# Sheet1.net
KiCad netlist of a schematic drawn in Altium Designer
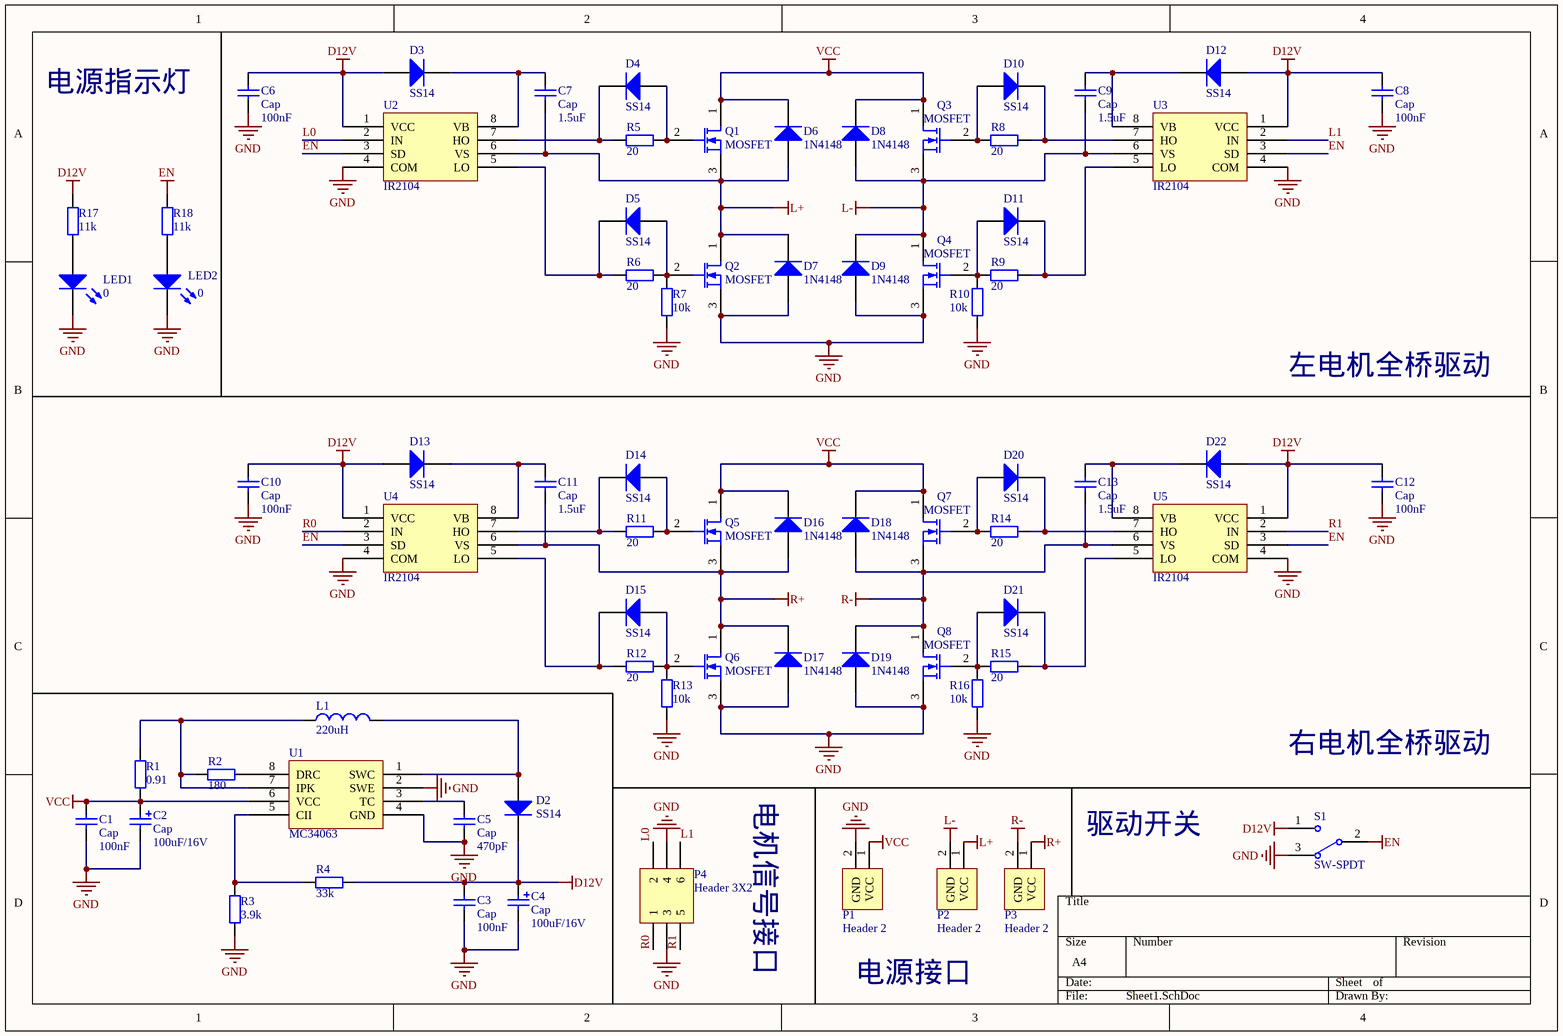
[diagram p0: Sheet1.SchDoc]

(export (version "E")
  (design (tool "Eeschema 10.0.6"))
  (components
    (comp (ref "C1")
      (value "Cap")
      (footprint "0603C")
      (description "Capacitor")
      (fields (field (name "ALTIUM_VALUE") "100nF") (field (name "PUBLISHER") "Altium Limited"))
      (libsource (lib "Schlib1") (part "Cap"))
    )
    (comp (ref "C2")
      (value "Cap")
      (footprint "电解电容")
      (description "Capacitor")
      (fields (field (name "ALTIUM_VALUE") "100uF/16V") (field (name "PUBLISHER") "Altium Limited"))
      (libsource (lib "Schlib1") (part "Cap2"))
    )
    (comp (ref "C3")
      (value "Cap")
      (footprint "0603C")
      (description "Capacitor")
      (fields (field (name "ALTIUM_VALUE") "100nF") (field (name "PUBLISHER") "Altium Limited"))
      (libsource (lib "Schlib1") (part "Cap"))
    )
    (comp (ref "C4")
      (value "Cap")
      (footprint "电解电容")
      (description "Capacitor")
      (fields (field (name "ALTIUM_VALUE") "100uF/16V") (field (name "PUBLISHER") "Altium Limited"))
      (libsource (lib "Schlib1") (part "Cap2"))
    )
    (comp (ref "C5")
      (value "Cap")
      (footprint "0603C")
      (description "Capacitor")
      (fields (field (name "ALTIUM_VALUE") "470pF") (field (name "PUBLISHER") "Altium Limited"))
      (libsource (lib "Schlib1") (part "Cap"))
    )
    (comp (ref "C6")
      (value "Cap")
      (footprint "0603C")
      (description "Capacitor")
      (fields (field (name "ALTIUM_VALUE") "100nF") (field (name "PUBLISHER") "Altium Limited"))
      (libsource (lib "Schlib1") (part "Cap"))
    )
    (comp (ref "C7")
      (value "Cap")
      (footprint "0603C")
      (description "Capacitor")
      (fields (field (name "ALTIUM_VALUE") "1.5uF") (field (name "PUBLISHER") "Altium Limited"))
      (libsource (lib "Schlib1") (part "Cap"))
    )
    (comp (ref "C8")
      (value "Cap")
      (footprint "0603C")
      (description "Capacitor")
      (fields (field (name "ALTIUM_VALUE") "100nF") (field (name "PUBLISHER") "Altium Limited"))
      (libsource (lib "Schlib1") (part "Cap"))
    )
    (comp (ref "C9")
      (value "Cap")
      (footprint "0603C")
      (description "Capacitor")
      (fields (field (name "ALTIUM_VALUE") "1.5uF") (field (name "PUBLISHER") "Altium Limited"))
      (libsource (lib "Schlib1") (part "Cap"))
    )
    (comp (ref "C10")
      (value "Cap")
      (footprint "0603C")
      (description "Capacitor")
      (fields (field (name "ALTIUM_VALUE") "100nF") (field (name "PUBLISHER") "Altium Limited"))
      (libsource (lib "Schlib1") (part "Cap"))
    )
    (comp (ref "C11")
      (value "Cap")
      (footprint "0603C")
      (description "Capacitor")
      (fields (field (name "ALTIUM_VALUE") "1.5uF") (field (name "PUBLISHER") "Altium Limited"))
      (libsource (lib "Schlib1") (part "Cap"))
    )
    (comp (ref "C12")
      (value "Cap")
      (footprint "0603C")
      (description "Capacitor")
      (fields (field (name "ALTIUM_VALUE") "100nF") (field (name "PUBLISHER") "Altium Limited"))
      (libsource (lib "Schlib1") (part "Cap"))
    )
    (comp (ref "C13")
      (value "Cap")
      (footprint "0603C")
      (description "Capacitor")
      (fields (field (name "ALTIUM_VALUE") "1.5uF") (field (name "PUBLISHER") "Altium Limited"))
      (libsource (lib "Schlib1") (part "Cap"))
    )
    (comp (ref "D2")
      (value "SS14")
      (footprint "ss54")
      (description "Default Diode")
      (fields (field (name "PUBLISHER") "Altium Limited"))
      (libsource (lib "Schlib1") (part "Diode_1"))
    )
    (comp (ref "D3")
      (value "SS14")
      (footprint "ss54")
      (description "Default Diode")
      (fields (field (name "PUBLISHER") "Altium Limited"))
      (libsource (lib "Schlib1") (part "Diode_1"))
    )
    (comp (ref "D4")
      (value "SS14")
      (footprint "ss54")
      (description "Default Diode")
      (fields (field (name "PUBLISHER") "Altium Limited"))
      (libsource (lib "Schlib1") (part "Diode_1"))
    )
    (comp (ref "D5")
      (value "SS14")
      (footprint "ss54")
      (description "Default Diode")
      (fields (field (name "PUBLISHER") "Altium Limited"))
      (libsource (lib "Schlib1") (part "Diode_1"))
    )
    (comp (ref "D6")
      (value "1N4148")
      (footprint "SOD123")
      (description "Default Diode")
      (fields (field (name "PUBLISHER") "Altium Limited"))
      (libsource (lib "Schlib1") (part "Diode_2"))
    )
    (comp (ref "D7")
      (value "1N4148")
      (footprint "SOD123")
      (description "Default Diode")
      (fields (field (name "PUBLISHER") "Altium Limited"))
      (libsource (lib "Schlib1") (part "Diode_2"))
    )
    (comp (ref "D8")
      (value "1N4148")
      (footprint "SOD123")
      (description "Default Diode")
      (fields (field (name "PUBLISHER") "Altium Limited"))
      (libsource (lib "Schlib1") (part "Diode_2"))
    )
    (comp (ref "D9")
      (value "1N4148")
      (footprint "SOD123")
      (description "Default Diode")
      (fields (field (name "PUBLISHER") "Altium Limited"))
      (libsource (lib "Schlib1") (part "Diode_2"))
    )
    (comp (ref "D10")
      (value "SS14")
      (footprint "ss54")
      (description "Default Diode")
      (fields (field (name "PUBLISHER") "Altium Limited"))
      (libsource (lib "Schlib1") (part "Diode_1"))
    )
    (comp (ref "D11")
      (value "SS14")
      (footprint "ss54")
      (description "Default Diode")
      (fields (field (name "PUBLISHER") "Altium Limited"))
      (libsource (lib "Schlib1") (part "Diode_1"))
    )
    (comp (ref "D12")
      (value "SS14")
      (footprint "ss54")
      (description "Default Diode")
      (fields (field (name "PUBLISHER") "Altium Limited"))
      (libsource (lib "Schlib1") (part "Diode_1"))
    )
    (comp (ref "D13")
      (value "SS14")
      (footprint "ss54")
      (description "Default Diode")
      (fields (field (name "PUBLISHER") "Altium Limited"))
      (libsource (lib "Schlib1") (part "Diode_1"))
    )
    (comp (ref "D14")
      (value "SS14")
      (footprint "ss54")
      (description "Default Diode")
      (fields (field (name "PUBLISHER") "Altium Limited"))
      (libsource (lib "Schlib1") (part "Diode_1"))
    )
    (comp (ref "D15")
      (value "SS14")
      (footprint "ss54")
      (description "Default Diode")
      (fields (field (name "PUBLISHER") "Altium Limited"))
      (libsource (lib "Schlib1") (part "Diode_1"))
    )
    (comp (ref "D16")
      (value "1N4148")
      (footprint "SOD123")
      (description "Default Diode")
      (fields (field (name "PUBLISHER") "Altium Limited"))
      (libsource (lib "Schlib1") (part "Diode_2"))
    )
    (comp (ref "D17")
      (value "1N4148")
      (footprint "SOD123")
      (description "Default Diode")
      (fields (field (name "PUBLISHER") "Altium Limited"))
      (libsource (lib "Schlib1") (part "Diode_2"))
    )
    (comp (ref "D18")
      (value "1N4148")
      (footprint "SOD123")
      (description "Default Diode")
      (fields (field (name "PUBLISHER") "Altium Limited"))
      (libsource (lib "Schlib1") (part "Diode_2"))
    )
    (comp (ref "D19")
      (value "1N4148")
      (footprint "SOD123")
      (description "Default Diode")
      (fields (field (name "PUBLISHER") "Altium Limited"))
      (libsource (lib "Schlib1") (part "Diode_2"))
    )
    (comp (ref "D20")
      (value "SS14")
      (footprint "ss54")
      (description "Default Diode")
      (fields (field (name "PUBLISHER") "Altium Limited"))
      (libsource (lib "Schlib1") (part "Diode_1"))
    )
    (comp (ref "D21")
      (value "SS14")
      (footprint "ss54")
      (description "Default Diode")
      (fields (field (name "PUBLISHER") "Altium Limited"))
      (libsource (lib "Schlib1") (part "Diode_1"))
    )
    (comp (ref "D22")
      (value "SS14")
      (footprint "ss54")
      (description "Default Diode")
      (fields (field (name "PUBLISHER") "Altium Limited"))
      (libsource (lib "Schlib1") (part "Diode_1"))
    )
    (comp (ref "L1")
      (value "220uH")
      (footprint "cd54")
      (description "Inductor")
      (fields (field (name "PUBLISHER") "Altium Limited"))
      (libsource (lib "Schlib1") (part "Inductor_2"))
    )
    (comp (ref "LED1")
      (value "0")
      (footprint "0603C")
      (description "Typical RED, GREEN, YELLOW, AMBER GaAs LED")
      (fields (field (name "PUBLISHER") "Altium Limited"))
      (libsource (lib "Schlib1") (part "LED2"))
    )
    (comp (ref "LED2")
      (value "0")
      (footprint "0603C")
      (description "Typical RED, GREEN, YELLOW, AMBER GaAs LED")
      (fields (field (name "PUBLISHER") "Altium Limited"))
      (libsource (lib "Schlib1") (part "LED2"))
    )
    (comp (ref "P1")
      (value "Header 2")
      (footprint "VCCBAT")
      (description "Header, 2-Pin")
      (fields (field (name "PUBLISHER") "Altium Limited"))
      (libsource (lib "Schlib1") (part "Header 2_2"))
    )
    (comp (ref "P2")
      (value "Header 2")
      (footprint "VCCBAT")
      (description "Header, 2-Pin")
      (fields (field (name "PUBLISHER") "Altium Limited"))
      (libsource (lib "Schlib1") (part "Header 2_2"))
    )
    (comp (ref "P3")
      (value "Header 2")
      (footprint "VCCBAT")
      (description "Header, 2-Pin")
      (fields (field (name "PUBLISHER") "Altium Limited"))
      (libsource (lib "Schlib1") (part "Header 2_2"))
    )
    (comp (ref "P4")
      (value "Header 3X2")
      (footprint "HDR2X3")
      (description "Header, 3-Pin, Dual row")
      (fields (field (name "PUBLISHER") "Altium Limited"))
      (libsource (lib "Miscellaneous Connectors") (part "Header 3X2"))
    )
    (comp (ref "Q1") (value "MOSFET") (footprint "DPAK-1") (libsource (lib "Schlib1") (part "MOSFET-N")))
    (comp (ref "Q2") (value "MOSFET") (footprint "DPAK-1") (libsource (lib "Schlib1") (part "MOSFET-N")))
    (comp (ref "Q3") (value "MOSFET") (footprint "DPAK-1") (libsource (lib "Schlib1") (part "MOSFET-N")))
    (comp (ref "Q4") (value "MOSFET") (footprint "DPAK-1") (libsource (lib "Schlib1") (part "MOSFET-N")))
    (comp (ref "Q5") (value "MOSFET") (footprint "DPAK-1") (libsource (lib "Schlib1") (part "MOSFET-N")))
    (comp (ref "Q6") (value "MOSFET") (footprint "DPAK-1") (libsource (lib "Schlib1") (part "MOSFET-N")))
    (comp (ref "Q7") (value "MOSFET") (footprint "DPAK-1") (libsource (lib "Schlib1") (part "MOSFET-N")))
    (comp (ref "Q8") (value "MOSFET") (footprint "DPAK-1") (libsource (lib "Schlib1") (part "MOSFET-N")))
    (comp (ref "R1")
      (value "0.91")
      (footprint "0603R")
      (description "Resistor")
      (fields (field (name "Comment") "Res2") (field (name "PUBLISHER") "Altium Limited"))
      (libsource (lib "") (part "Res2_2"))
    )
    (comp (ref "R2")
      (value "180")
      (footprint "0603R")
      (description "Resistor")
      (fields (field (name "Comment") "Res2") (field (name "PUBLISHER") "Altium Limited"))
      (libsource (lib "") (part "Res2_1"))
    )
    (comp (ref "R3")
      (value "3.9k")
      (footprint "0603R")
      (description "Resistor")
      (fields (field (name "Comment") "Res2") (field (name "PUBLISHER") "Altium Limited"))
      (libsource (lib "Schlib1") (part "Res2"))
    )
    (comp (ref "R4")
      (value "33k")
      (footprint "0603R")
      (description "Resistor")
      (fields (field (name "Comment") "Res2") (field (name "PUBLISHER") "Altium Limited"))
      (libsource (lib "") (part "Res2_1"))
    )
    (comp (ref "R5")
      (value "20")
      (footprint "0603R")
      (description "Resistor")
      (fields (field (name "Comment") "Res2") (field (name "PUBLISHER") "Altium Limited"))
      (libsource (lib "") (part "Res2_1"))
    )
    (comp (ref "R6")
      (value "20")
      (footprint "0603R")
      (description "Resistor")
      (fields (field (name "Comment") "Res2") (field (name "PUBLISHER") "Altium Limited"))
      (libsource (lib "") (part "Res2_1"))
    )
    (comp (ref "R7")
      (value "10k")
      (footprint "0603R")
      (description "Resistor")
      (fields (field (name "Comment") "Res2") (field (name "PUBLISHER") "Altium Limited"))
      (libsource (lib "") (part "Res2_2"))
    )
    (comp (ref "R8")
      (value "20")
      (footprint "0603R")
      (description "Resistor")
      (fields (field (name "Comment") "Res2") (field (name "PUBLISHER") "Altium Limited"))
      (libsource (lib "") (part "Res2_2"))
    )
    (comp (ref "R9")
      (value "20")
      (footprint "0603R")
      (description "Resistor")
      (fields (field (name "Comment") "Res2") (field (name "PUBLISHER") "Altium Limited"))
      (libsource (lib "") (part "Res2_2"))
    )
    (comp (ref "R10")
      (value "10k")
      (footprint "0603R")
      (description "Resistor")
      (fields (field (name "Comment") "Res2") (field (name "PUBLISHER") "Altium Limited"))
      (libsource (lib "") (part "Res2_3"))
    )
    (comp (ref "R11")
      (value "20")
      (footprint "0603R")
      (description "Resistor")
      (fields (field (name "Comment") "Res2") (field (name "PUBLISHER") "Altium Limited"))
      (libsource (lib "") (part "Res2_1"))
    )
    (comp (ref "R12")
      (value "20")
      (footprint "0603R")
      (description "Resistor")
      (fields (field (name "Comment") "Res2") (field (name "PUBLISHER") "Altium Limited"))
      (libsource (lib "") (part "Res2_1"))
    )
    (comp (ref "R13")
      (value "10k")
      (footprint "0603R")
      (description "Resistor")
      (fields (field (name "Comment") "Res2") (field (name "PUBLISHER") "Altium Limited"))
      (libsource (lib "") (part "Res2_2"))
    )
    (comp (ref "R14")
      (value "20")
      (footprint "0603R")
      (description "Resistor")
      (fields (field (name "Comment") "Res2") (field (name "PUBLISHER") "Altium Limited"))
      (libsource (lib "") (part "Res2_2"))
    )
    (comp (ref "R15")
      (value "20")
      (footprint "0603R")
      (description "Resistor")
      (fields (field (name "Comment") "Res2") (field (name "PUBLISHER") "Altium Limited"))
      (libsource (lib "") (part "Res2_2"))
    )
    (comp (ref "R16")
      (value "10k")
      (footprint "0603R")
      (description "Resistor")
      (fields (field (name "Comment") "Res2") (field (name "PUBLISHER") "Altium Limited"))
      (libsource (lib "") (part "Res2_3"))
    )
    (comp (ref "R17")
      (value "11k")
      (footprint "0603R")
      (description "Resistor")
      (fields (field (name "Comment") "Res2") (field (name "PUBLISHER") "Altium Limited"))
      (libsource (lib "") (part "Res2_2"))
    )
    (comp (ref "R18")
      (value "11k")
      (footprint "0603R")
      (description "Resistor")
      (fields (field (name "Comment") "Res2") (field (name "PUBLISHER") "Altium Limited"))
      (libsource (lib "") (part "Res2_2"))
    )
    (comp (ref "S1")
      (value "SW-SPDT")
      (footprint "SW")
      (description "SPDT Subminiature Toggle Switch, Right Angle Mounting, Vertical Actuation")
      (fields (field (name "PUBLISHER") "Altium Limited"))
      (libsource (lib "Miscellaneous Devices") (part "SW-SPDT"))
    )
    (comp (ref "U1") (value "MC34063") (footprint "SOIC-8") (libsource (lib "Schlib1") (part "MC34063")))
    (comp (ref "U2") (value "IR2104") (footprint "SOIC-8") (libsource (lib "Schlib1") (part "IR2104")))
    (comp (ref "U3") (value "IR2104") (footprint "SOIC-8") (libsource (lib "") (part "IR2104_1")))
    (comp (ref "U4") (value "IR2104") (footprint "SOIC-8") (libsource (lib "Schlib1") (part "IR2104")))
    (comp (ref "U5") (value "IR2104") (footprint "SOIC-8") (libsource (lib "") (part "IR2104_1")))
  )
  (nets
    (net (code "1") (name "/L0") (class "Default")
      (node (ref "P4") (pin "2") (pinfunction "2_2") (pintype "passive"))
      (node (ref "U2") (pin "2") (pinfunction "IN_2") (pintype "passive"))
    )
    (net (code "2") (name "/L1") (class "Default")
      (node (ref "P4") (pin "6") (pinfunction "6_6") (pintype "passive"))
      (node (ref "U3") (pin "2") (pinfunction "IN_2") (pintype "passive"))
    )
    (net (code "3") (name "/R0") (class "Default")
      (node (ref "P4") (pin "1") (pinfunction "1_1") (pintype "passive"))
      (node (ref "U4") (pin "2") (pinfunction "IN_2") (pintype "passive"))
    )
    (net (code "4") (name "/R1") (class "Default")
      (node (ref "P4") (pin "5") (pinfunction "5_5") (pintype "passive"))
      (node (ref "U5") (pin "2") (pinfunction "IN_2") (pintype "passive"))
    )
    (net (code "5") (name "D12V") (class "Default")
      (node (ref "C10") (pin "2") (pinfunction "2_2") (pintype "passive"))
      (node (ref "C12") (pin "2") (pinfunction "2_2") (pintype "passive"))
      (node (ref "C3") (pin "2") (pinfunction "2_2") (pintype "passive"))
      (node (ref "C4") (pin "1") (pinfunction "1_1") (pintype "passive"))
      (node (ref "C6") (pin "2") (pinfunction "2_2") (pintype "passive"))
      (node (ref "C8") (pin "2") (pinfunction "2_2") (pintype "passive"))
      (node (ref "D12") (pin "1") (pinfunction "A_1") (pintype "passive"))
      (node (ref "D13") (pin "1") (pinfunction "A_1") (pintype "passive"))
      (node (ref "D2") (pin "2") (pinfunction "K_2") (pintype "passive"))
      (node (ref "D22") (pin "1") (pinfunction "A_1") (pintype "passive"))
      (node (ref "D3") (pin "1") (pinfunction "A_1") (pintype "passive"))
      (node (ref "R17") (pin "2") (pinfunction "2_2") (pintype "passive"))
      (node (ref "R4") (pin "1") (pinfunction "1_1") (pintype "passive"))
      (node (ref "S1") (pin "1") (pinfunction "1_1") (pintype "passive"))
      (node (ref "U2") (pin "1") (pinfunction "VCC_1") (pintype "passive"))
      (node (ref "U3") (pin "1") (pinfunction "VCC_1") (pintype "passive"))
      (node (ref "U4") (pin "1") (pinfunction "VCC_1") (pintype "passive"))
      (node (ref "U5") (pin "1") (pinfunction "VCC_1") (pintype "passive"))
    )
    (net (code "6") (name "EN") (class "Default")
      (node (ref "R18") (pin "2") (pinfunction "2_2") (pintype "passive"))
      (node (ref "S1") (pin "2") (pinfunction "2_2") (pintype "passive"))
      (node (ref "U2") (pin "3") (pinfunction "SD_3") (pintype "passive"))
      (node (ref "U3") (pin "3") (pinfunction "SD_3") (pintype "passive"))
      (node (ref "U4") (pin "3") (pinfunction "SD_3") (pintype "passive"))
      (node (ref "U5") (pin "3") (pinfunction "SD_3") (pintype "passive"))
    )
    (net (code "7") (name "GND") (class "Default")
      (node (ref "C1") (pin "1") (pinfunction "1_1") (pintype "passive"))
      (node (ref "C10") (pin "1") (pinfunction "1_1") (pintype "passive"))
      (node (ref "C12") (pin "1") (pinfunction "1_1") (pintype "passive"))
      (node (ref "C2") (pin "2") (pinfunction "2_2") (pintype "passive"))
      (node (ref "C3") (pin "1") (pinfunction "1_1") (pintype "passive"))
      (node (ref "C4") (pin "2") (pinfunction "2_2") (pintype "passive"))
      (node (ref "C5") (pin "1") (pinfunction "1_1") (pintype "passive"))
      (node (ref "C6") (pin "1") (pinfunction "1_1") (pintype "passive"))
      (node (ref "C8") (pin "1") (pinfunction "1_1") (pintype "passive"))
      (node (ref "D17") (pin "1") (pinfunction "A_1") (pintype "passive"))
      (node (ref "D19") (pin "1") (pinfunction "A_1") (pintype "passive"))
      (node (ref "D7") (pin "1") (pinfunction "A_1") (pintype "passive"))
      (node (ref "D9") (pin "1") (pinfunction "A_1") (pintype "passive"))
      (node (ref "LED1") (pin "2") (pinfunction "K_2") (pintype "passive"))
      (node (ref "LED2") (pin "2") (pinfunction "K_2") (pintype "passive"))
      (node (ref "P1") (pin "2") (pinfunction "GND_2") (pintype "passive"))
      (node (ref "P4") (pin "3") (pinfunction "3_3") (pintype "passive"))
      (node (ref "P4") (pin "4") (pinfunction "4_4") (pintype "passive"))
      (node (ref "Q2") (pin "3") (pinfunction "3_3") (pintype "passive"))
      (node (ref "Q4") (pin "3") (pinfunction "3_3") (pintype "passive"))
      (node (ref "Q6") (pin "3") (pinfunction "3_3") (pintype "passive"))
      (node (ref "Q8") (pin "3") (pinfunction "3_3") (pintype "passive"))
      (node (ref "R10") (pin "1") (pinfunction "1_1") (pintype "passive"))
      (node (ref "R13") (pin "1") (pinfunction "1_1") (pintype "passive"))
      (node (ref "R16") (pin "1") (pinfunction "1_1") (pintype "passive"))
      (node (ref "R3") (pin "2") (pinfunction "2_2") (pintype "passive"))
      (node (ref "R7") (pin "1") (pinfunction "1_1") (pintype "passive"))
      (node (ref "S1") (pin "3") (pinfunction "3_3") (pintype "passive"))
      (node (ref "U1") (pin "2") (pinfunction "SWE_2") (pintype "passive"))
      (node (ref "U1") (pin "4") (pinfunction "GND_4") (pintype "passive"))
      (node (ref "U2") (pin "4") (pinfunction "COM_4") (pintype "passive"))
      (node (ref "U3") (pin "4") (pinfunction "COM_4") (pintype "passive"))
      (node (ref "U4") (pin "4") (pinfunction "COM_4") (pintype "passive"))
      (node (ref "U5") (pin "4") (pinfunction "COM_4") (pintype "passive"))
    )
    (net (code "8") (name "L+") (class "Default")
      (node (ref "C7") (pin "1") (pinfunction "1_1") (pintype "passive"))
      (node (ref "D6") (pin "1") (pinfunction "A_1") (pintype "passive"))
      (node (ref "D7") (pin "2") (pinfunction "K_2") (pintype "passive"))
      (node (ref "P2") (pin "1") (pinfunction "VCC_1") (pintype "passive"))
      (node (ref "Q1") (pin "3") (pinfunction "3_3") (pintype "passive"))
      (node (ref "Q2") (pin "1") (pinfunction "D_1") (pintype "passive"))
      (node (ref "U2") (pin "6") (pinfunction "VS_6") (pintype "passive"))
    )
    (net (code "9") (name "L-") (class "Default")
      (node (ref "C9") (pin "1") (pinfunction "1_1") (pintype "passive"))
      (node (ref "D8") (pin "1") (pinfunction "A_1") (pintype "passive"))
      (node (ref "D9") (pin "2") (pinfunction "K_2") (pintype "passive"))
      (node (ref "P2") (pin "2") (pinfunction "GND_2") (pintype "passive"))
      (node (ref "Q3") (pin "3") (pinfunction "3_3") (pintype "passive"))
      (node (ref "Q4") (pin "1") (pinfunction "D_1") (pintype "passive"))
      (node (ref "U3") (pin "6") (pinfunction "VS_6") (pintype "passive"))
    )
    (net (code "10") (name "Net-(D2-A)") (class "Default")
      (node (ref "D2") (pin "1") (pinfunction "A_1") (pintype "passive"))
      (node (ref "L1") (pin "2") (pinfunction "2_2") (pintype "passive"))
      (node (ref "U1") (pin "1") (pinfunction "SWC_1") (pintype "passive"))
    )
    (net (code "11") (name "Net-(D3-K)") (class "Default")
      (node (ref "C7") (pin "2") (pinfunction "2_2") (pintype "passive"))
      (node (ref "D3") (pin "2") (pinfunction "K_2") (pintype "passive"))
      (node (ref "U2") (pin "8") (pinfunction "VB_8") (pintype "passive"))
    )
    (net (code "12") (name "Net-(D4-A)") (class "Default")
      (node (ref "D4") (pin "1") (pinfunction "A_1") (pintype "passive"))
      (node (ref "Q1") (pin "2") (pinfunction "G_2") (pintype "passive"))
      (node (ref "R5") (pin "1") (pinfunction "1_1") (pintype "passive"))
    )
    (net (code "13") (name "Net-(D4-K)") (class "Default")
      (node (ref "D4") (pin "2") (pinfunction "K_2") (pintype "passive"))
      (node (ref "R5") (pin "2") (pinfunction "2_2") (pintype "passive"))
      (node (ref "U2") (pin "7") (pinfunction "HO_7") (pintype "passive"))
    )
    (net (code "14") (name "Net-(D5-A)") (class "Default")
      (node (ref "D5") (pin "1") (pinfunction "A_1") (pintype "passive"))
      (node (ref "Q2") (pin "2") (pinfunction "G_2") (pintype "passive"))
      (node (ref "R6") (pin "1") (pinfunction "1_1") (pintype "passive"))
      (node (ref "R7") (pin "2") (pinfunction "2_2") (pintype "passive"))
    )
    (net (code "15") (name "Net-(D5-K)") (class "Default")
      (node (ref "D5") (pin "2") (pinfunction "K_2") (pintype "passive"))
      (node (ref "R6") (pin "2") (pinfunction "2_2") (pintype "passive"))
      (node (ref "U2") (pin "5") (pinfunction "LO_5") (pintype "passive"))
    )
    (net (code "16") (name "Net-(D10-A)") (class "Default")
      (node (ref "D10") (pin "1") (pinfunction "A_1") (pintype "passive"))
      (node (ref "Q3") (pin "2") (pinfunction "G_2") (pintype "passive"))
      (node (ref "R8") (pin "1") (pinfunction "1_1") (pintype "passive"))
    )
    (net (code "17") (name "Net-(D10-K)") (class "Default")
      (node (ref "D10") (pin "2") (pinfunction "K_2") (pintype "passive"))
      (node (ref "R8") (pin "2") (pinfunction "2_2") (pintype "passive"))
      (node (ref "U3") (pin "7") (pinfunction "HO_7") (pintype "passive"))
    )
    (net (code "18") (name "Net-(D11-A)") (class "Default")
      (node (ref "D11") (pin "1") (pinfunction "A_1") (pintype "passive"))
      (node (ref "Q4") (pin "2") (pinfunction "G_2") (pintype "passive"))
      (node (ref "R10") (pin "2") (pinfunction "2_2") (pintype "passive"))
      (node (ref "R9") (pin "1") (pinfunction "1_1") (pintype "passive"))
    )
    (net (code "19") (name "Net-(D11-K)") (class "Default")
      (node (ref "D11") (pin "2") (pinfunction "K_2") (pintype "passive"))
      (node (ref "R9") (pin "2") (pinfunction "2_2") (pintype "passive"))
      (node (ref "U3") (pin "5") (pinfunction "LO_5") (pintype "passive"))
    )
    (net (code "20") (name "Net-(D12-K)") (class "Default")
      (node (ref "C9") (pin "2") (pinfunction "2_2") (pintype "passive"))
      (node (ref "D12") (pin "2") (pinfunction "K_2") (pintype "passive"))
      (node (ref "U3") (pin "8") (pinfunction "VB_8") (pintype "passive"))
    )
    (net (code "21") (name "Net-(D13-K)") (class "Default")
      (node (ref "C11") (pin "2") (pinfunction "2_2") (pintype "passive"))
      (node (ref "D13") (pin "2") (pinfunction "K_2") (pintype "passive"))
      (node (ref "U4") (pin "8") (pinfunction "VB_8") (pintype "passive"))
    )
    (net (code "22") (name "Net-(D14-A)") (class "Default")
      (node (ref "D14") (pin "1") (pinfunction "A_1") (pintype "passive"))
      (node (ref "Q5") (pin "2") (pinfunction "G_2") (pintype "passive"))
      (node (ref "R11") (pin "1") (pinfunction "1_1") (pintype "passive"))
    )
    (net (code "23") (name "Net-(D14-K)") (class "Default")
      (node (ref "D14") (pin "2") (pinfunction "K_2") (pintype "passive"))
      (node (ref "R11") (pin "2") (pinfunction "2_2") (pintype "passive"))
      (node (ref "U4") (pin "7") (pinfunction "HO_7") (pintype "passive"))
    )
    (net (code "24") (name "Net-(D15-A)") (class "Default")
      (node (ref "D15") (pin "1") (pinfunction "A_1") (pintype "passive"))
      (node (ref "Q6") (pin "2") (pinfunction "G_2") (pintype "passive"))
      (node (ref "R12") (pin "1") (pinfunction "1_1") (pintype "passive"))
      (node (ref "R13") (pin "2") (pinfunction "2_2") (pintype "passive"))
    )
    (net (code "25") (name "Net-(D15-K)") (class "Default")
      (node (ref "D15") (pin "2") (pinfunction "K_2") (pintype "passive"))
      (node (ref "R12") (pin "2") (pinfunction "2_2") (pintype "passive"))
      (node (ref "U4") (pin "5") (pinfunction "LO_5") (pintype "passive"))
    )
    (net (code "26") (name "Net-(D20-A)") (class "Default")
      (node (ref "D20") (pin "1") (pinfunction "A_1") (pintype "passive"))
      (node (ref "Q7") (pin "2") (pinfunction "G_2") (pintype "passive"))
      (node (ref "R14") (pin "1") (pinfunction "1_1") (pintype "passive"))
    )
    (net (code "27") (name "Net-(D20-K)") (class "Default")
      (node (ref "D20") (pin "2") (pinfunction "K_2") (pintype "passive"))
      (node (ref "R14") (pin "2") (pinfunction "2_2") (pintype "passive"))
      (node (ref "U5") (pin "7") (pinfunction "HO_7") (pintype "passive"))
    )
    (net (code "28") (name "Net-(D21-A)") (class "Default")
      (node (ref "D21") (pin "1") (pinfunction "A_1") (pintype "passive"))
      (node (ref "Q8") (pin "2") (pinfunction "G_2") (pintype "passive"))
      (node (ref "R15") (pin "1") (pinfunction "1_1") (pintype "passive"))
      (node (ref "R16") (pin "2") (pinfunction "2_2") (pintype "passive"))
    )
    (net (code "29") (name "Net-(D21-K)") (class "Default")
      (node (ref "D21") (pin "2") (pinfunction "K_2") (pintype "passive"))
      (node (ref "R15") (pin "2") (pinfunction "2_2") (pintype "passive"))
      (node (ref "U5") (pin "5") (pinfunction "LO_5") (pintype "passive"))
    )
    (net (code "30") (name "Net-(D22-K)") (class "Default")
      (node (ref "C13") (pin "2") (pinfunction "2_2") (pintype "passive"))
      (node (ref "D22") (pin "2") (pinfunction "K_2") (pintype "passive"))
      (node (ref "U5") (pin "8") (pinfunction "VB_8") (pintype "passive"))
    )
    (net (code "31") (name "Net-(LED1-A)") (class "Default")
      (node (ref "LED1") (pin "1") (pinfunction "A_1") (pintype "passive"))
      (node (ref "R17") (pin "1") (pinfunction "1_1") (pintype "passive"))
    )
    (net (code "32") (name "Net-(LED2-A)") (class "Default")
      (node (ref "LED2") (pin "1") (pinfunction "A_1") (pintype "passive"))
      (node (ref "R18") (pin "1") (pinfunction "1_1") (pintype "passive"))
    )
    (net (code "33") (name "Net-(U1-CII)") (class "Default")
      (node (ref "R3") (pin "1") (pinfunction "1_1") (pintype "passive"))
      (node (ref "R4") (pin "2") (pinfunction "2_2") (pintype "passive"))
      (node (ref "U1") (pin "5") (pinfunction "CII_5") (pintype "passive"))
    )
    (net (code "34") (name "Net-(U1-DRC)") (class "Default")
      (node (ref "R2") (pin "1") (pinfunction "1_1") (pintype "passive"))
      (node (ref "U1") (pin "8") (pinfunction "DRC_8") (pintype "passive"))
    )
    (net (code "35") (name "Net-(U1-IPK)") (class "Default")
      (node (ref "L1") (pin "1") (pinfunction "1_1") (pintype "passive"))
      (node (ref "R1") (pin "2") (pinfunction "2_2") (pintype "passive"))
      (node (ref "R2") (pin "2") (pinfunction "2_2") (pintype "passive"))
      (node (ref "U1") (pin "7") (pinfunction "IPK_7") (pintype "passive"))
    )
    (net (code "36") (name "Net-(U1-TC)") (class "Default")
      (node (ref "C5") (pin "2") (pinfunction "2_2") (pintype "passive"))
      (node (ref "U1") (pin "3") (pinfunction "TC_3") (pintype "passive"))
    )
    (net (code "37") (name "R+") (class "Default")
      (node (ref "C11") (pin "1") (pinfunction "1_1") (pintype "passive"))
      (node (ref "D16") (pin "1") (pinfunction "A_1") (pintype "passive"))
      (node (ref "D17") (pin "2") (pinfunction "K_2") (pintype "passive"))
      (node (ref "P3") (pin "1") (pinfunction "VCC_1") (pintype "passive"))
      (node (ref "Q5") (pin "3") (pinfunction "3_3") (pintype "passive"))
      (node (ref "Q6") (pin "1") (pinfunction "D_1") (pintype "passive"))
      (node (ref "U4") (pin "6") (pinfunction "VS_6") (pintype "passive"))
    )
    (net (code "38") (name "R-") (class "Default")
      (node (ref "C13") (pin "1") (pinfunction "1_1") (pintype "passive"))
      (node (ref "D18") (pin "1") (pinfunction "A_1") (pintype "passive"))
      (node (ref "D19") (pin "2") (pinfunction "K_2") (pintype "passive"))
      (node (ref "P3") (pin "2") (pinfunction "GND_2") (pintype "passive"))
      (node (ref "Q7") (pin "3") (pinfunction "3_3") (pintype "passive"))
      (node (ref "Q8") (pin "1") (pinfunction "D_1") (pintype "passive"))
      (node (ref "U5") (pin "6") (pinfunction "VS_6") (pintype "passive"))
    )
    (net (code "39") (name "VCC") (class "Default")
      (node (ref "C1") (pin "2") (pinfunction "2_2") (pintype "passive"))
      (node (ref "C2") (pin "1") (pinfunction "1_1") (pintype "passive"))
      (node (ref "D16") (pin "2") (pinfunction "K_2") (pintype "passive"))
      (node (ref "D18") (pin "2") (pinfunction "K_2") (pintype "passive"))
      (node (ref "D6") (pin "2") (pinfunction "K_2") (pintype "passive"))
      (node (ref "D8") (pin "2") (pinfunction "K_2") (pintype "passive"))
      (node (ref "P1") (pin "1") (pinfunction "VCC_1") (pintype "passive"))
      (node (ref "Q1") (pin "1") (pinfunction "D_1") (pintype "passive"))
      (node (ref "Q3") (pin "1") (pinfunction "D_1") (pintype "passive"))
      (node (ref "Q5") (pin "1") (pinfunction "D_1") (pintype "passive"))
      (node (ref "Q7") (pin "1") (pinfunction "D_1") (pintype "passive"))
      (node (ref "R1") (pin "1") (pinfunction "1_1") (pintype "passive"))
      (node (ref "U1") (pin "6") (pinfunction "VCC_6") (pintype "passive"))
    )
  )
)
